# PCB_WOOD-WORKSHOP-REV1.net
KiCad netlist of a schematic drawn in Altium Designer
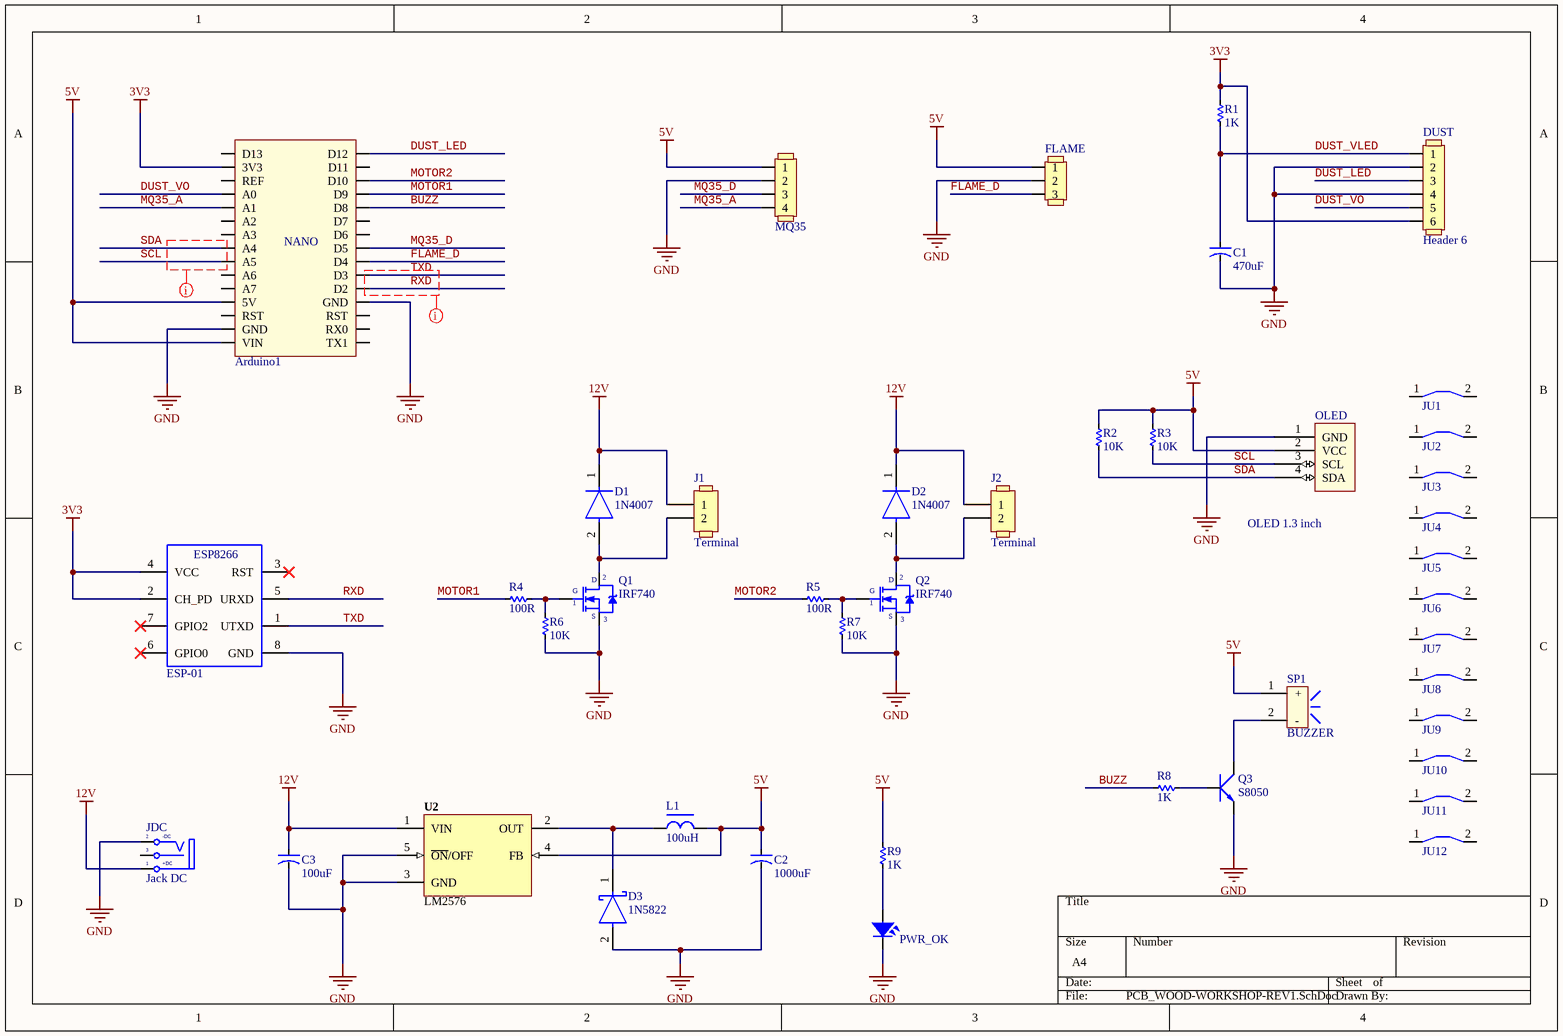
[diagram p0: PCB_WOOD-WORKSHOP-REV1.SchDoc]

(export (version "E")
  (design (tool "Eeschema 10.0.6"))
  (components
    (comp (ref "Arduino1")
      (value "Arduino Nano")
      (footprint "Arduino Nano")
      (description "Arduino NANO")
      (libsource (lib "LIBRARY_MuaLinhKien") (part "Arduino Nano"))
    )
    (comp (ref "C1")
      (value "470uF")
      (footprint "CA-ALU-6.3")
      (description "Capacitor (Semiconductor SIM Model)")
      (fields (field (name "PUBLISHER") "Altium Limited"))
      (libsource (lib "LIBRARY_MuaLinhKien") (part "CN-ALU-DIP"))
    )
    (comp (ref "C2")
      (value "1000uF")
      (footprint "CA-ALU-16")
      (description "Capacitor (Semiconductor SIM Model)")
      (fields (field (name "PUBLISHER") "Altium Limited"))
      (libsource (lib "LIBRARY_MuaLinhKien") (part "CN-ALU-DIP"))
    )
    (comp (ref "C3")
      (value "100uF")
      (footprint "CA-ALU-16")
      (description "Capacitor (Semiconductor SIM Model)")
      (fields (field (name "PUBLISHER") "Altium Limited"))
      (libsource (lib "LIBRARY_MuaLinhKien") (part "CN-ALU-DIP"))
    )
    (comp (ref "D1")
      (value "1N4007")
      (footprint "FP-1N4007-MFG")
      (description "Rectifier diode 1000 V 1 A DO-41, ,")
      (fields
        (field (name "MANUFACTURER") "Diotec")
        (field (name "OCTOPART") "https://octopart.com/1n4007-diotec-4040411")
      )
      (libsource (lib "Altium Content Vault") (part "d7152d700b627762746794eb795d46e"))
    )
    (comp (ref "D2")
      (value "1N4007")
      (footprint "FP-1N4007-MFG")
      (description "Rectifier diode 1000 V 1 A DO-41, ,")
      (fields
        (field (name "MANUFACTURER") "Diotec")
        (field (name "OCTOPART") "https://octopart.com/1n4007-diotec-4040411")
      )
      (libsource (lib "Altium Content Vault") (part "d7152d700b627762746794eb795d46e"))
    )
    (comp (ref "D3")
      (value "1N5822")
      (footprint "FP-DO-201AD-MFG")
      (description "DIODE SCHOTTKY 40V 3A DO201AD")
      (fields
        (field (name "OCTOPART") "https://octopart.com/1n5822-stmicroelectronics-323225")
        (field (name "MANUFACTURER") "STMicroelectronics")
      )
      (libsource (lib "Altium Content Vault") (part "1d6ec82d83fb6aee721767c19dac4b9"))
    )
    (comp (ref "DUST") (value "Header 6") (footprint "HEADER x6") (libsource (lib "Duc") (part "Header 6")))
    (comp (ref "FLAME") (value "Header 3") (footprint "HEADER x3") (libsource (lib "Duc") (part "Header 3")))
    (comp (ref "J1")
      (value "Terminal")
      (footprint "Terminal x2 5mm")
      (description "Terminal x2")
      (libsource (lib "Duc") (part "Terminal x2"))
    )
    (comp (ref "J2")
      (value "Terminal")
      (footprint "Terminal x2 5mm")
      (description "Terminal x2")
      (libsource (lib "Duc") (part "Terminal x2"))
    )
    (comp (ref "JDC")
      (value "Jack DC")
      (footprint "DC0")
      (description "Jac DC input")
      (libsource (lib "LIBRARY_MuaLinhKien") (part "DCIN"))
    )
    (comp (ref "JU1")
      (value "JUMPER 5MM")
      (footprint "JUMPER 10MM")
      (libsource (lib "tunaSchlib") (part "JUMPER 5MM"))
    )
    (comp (ref "JU2")
      (value "JUMPER 5MM")
      (footprint "JUMPER 10MM")
      (libsource (lib "tunaSchlib") (part "JUMPER 5MM"))
    )
    (comp (ref "JU3")
      (value "JUMPER 5MM")
      (footprint "JUMPER 10MM")
      (libsource (lib "tunaSchlib") (part "JUMPER 5MM"))
    )
    (comp (ref "JU4")
      (value "JUMPER 5MM")
      (footprint "JUMPER 5MM")
      (libsource (lib "tunaSchlib") (part "JUMPER 5MM"))
    )
    (comp (ref "JU5")
      (value "JUMPER 5MM")
      (footprint "JUMPER 5MM")
      (libsource (lib "tunaSchlib") (part "JUMPER 5MM"))
    )
    (comp (ref "JU6")
      (value "JUMPER 5MM")
      (footprint "JUMPER 15MM")
      (libsource (lib "tunaSchlib") (part "JUMPER 5MM"))
    )
    (comp (ref "JU7")
      (value "JUMPER 5MM")
      (footprint "JUMPER 15MM")
      (libsource (lib "tunaSchlib") (part "JUMPER 5MM"))
    )
    (comp (ref "JU8")
      (value "JUMPER 5MM")
      (footprint "JUMPER 10MM")
      (libsource (lib "tunaSchlib") (part "JUMPER 5MM"))
    )
    (comp (ref "JU9")
      (value "JUMPER 5MM")
      (footprint "JUMPER 5MM")
      (libsource (lib "tunaSchlib") (part "JUMPER 5MM"))
    )
    (comp (ref "JU10")
      (value "JUMPER 5MM")
      (footprint "JUMPER 15MM")
      (libsource (lib "tunaSchlib") (part "JUMPER 5MM"))
    )
    (comp (ref "JU11")
      (value "JUMPER 5MM")
      (footprint "JUMPER 10MM")
      (libsource (lib "tunaSchlib") (part "JUMPER 5MM"))
    )
    (comp (ref "JU12")
      (value "JUMPER 5MM")
      (footprint "JUMPER 15MM")
      (libsource (lib "tunaSchlib") (part "JUMPER 5MM"))
    )
    (comp (ref "L1")
      (value "100uH")
      (footprint "L-DIP-M-8")
      (description "Inductor")
      (libsource (lib "LIBRARY_MuaLinhKien") (part "L-DIP-1"))
    )
    (comp (ref "MQ35") (value "Header 4") (footprint "HEADER x4") (libsource (lib "Duc") (part "Header 4")))
    (comp (ref "OLED")
      (value "OLED 1.3 inch")
      (footprint "OLED 0.96 inch")
      (libsource (lib "tunaSchlib") (part "OLED 0.96 inch"))
    )
    (comp (ref "PWR_OK")
      (value "LED")
      (footprint "LED-5-RED")
      (description "LED Single colour Green and Red")
      (libsource (lib "LIBRARY_MuaLinhKien") (part "LED"))
    )
    (comp (ref "Q1")
      (value "IRF740")
      (footprint "TO220H1")
      (description "MOSFET N - CHANNEL 500V - 0.75 - 8A - TO-220")
      (libsource (lib "LIBRARY_MuaLinhKien") (part "IRF840"))
    )
    (comp (ref "Q2")
      (value "IRF740")
      (footprint "TO220H1")
      (description "MOSFET N - CHANNEL 500V - 0.75 - 8A - TO-220")
      (libsource (lib "LIBRARY_MuaLinhKien") (part "IRF840"))
    )
    (comp (ref "Q3")
      (value "S8050")
      (footprint "TO92-123")
      (description "NPN 600mW, ECB")
      (libsource (lib "LIBRARY_MuaLinhKien") (part "2SC1815"))
    )
    (comp (ref "R1")
      (value "1K")
      (footprint "RES-1/4W")
      (description "Res")
      (fields
        (field (name "MANUFACTURER") "Generic Components")
        (field (name "PUBLISHER") "Altium Hobart Technology Centre")
      )
      (libsource (lib "LIBRARY_MuaLinhKien") (part "Res"))
    )
    (comp (ref "R2")
      (value "10K")
      (footprint "RES-1/4W")
      (description "Res")
      (fields
        (field (name "MANUFACTURER") "Generic Components")
        (field (name "PUBLISHER") "Altium Hobart Technology Centre")
      )
      (libsource (lib "LIBRARY_MuaLinhKien") (part "Res"))
    )
    (comp (ref "R3")
      (value "10K")
      (footprint "RES-1/4W")
      (description "Res")
      (fields
        (field (name "MANUFACTURER") "Generic Components")
        (field (name "PUBLISHER") "Altium Hobart Technology Centre")
      )
      (libsource (lib "LIBRARY_MuaLinhKien") (part "Res"))
    )
    (comp (ref "R4")
      (value "100R")
      (footprint "RES-1/4W")
      (description "Res")
      (fields
        (field (name "MANUFACTURER") "Generic Components")
        (field (name "PUBLISHER") "Altium Hobart Technology Centre")
      )
      (libsource (lib "LIBRARY_MuaLinhKien") (part "Res"))
    )
    (comp (ref "R5")
      (value "100R")
      (footprint "RES-1/4W")
      (description "Res")
      (fields
        (field (name "MANUFACTURER") "Generic Components")
        (field (name "PUBLISHER") "Altium Hobart Technology Centre")
      )
      (libsource (lib "LIBRARY_MuaLinhKien") (part "Res"))
    )
    (comp (ref "R6")
      (value "10K")
      (footprint "RES-1/4W")
      (description "Res")
      (fields
        (field (name "MANUFACTURER") "Generic Components")
        (field (name "PUBLISHER") "Altium Hobart Technology Centre")
      )
      (libsource (lib "LIBRARY_MuaLinhKien") (part "Res"))
    )
    (comp (ref "R7")
      (value "10K")
      (footprint "RES-1/4W")
      (description "Res")
      (fields
        (field (name "MANUFACTURER") "Generic Components")
        (field (name "PUBLISHER") "Altium Hobart Technology Centre")
      )
      (libsource (lib "LIBRARY_MuaLinhKien") (part "Res"))
    )
    (comp (ref "R8")
      (value "1K")
      (footprint "RES-1/4W")
      (description "Res")
      (fields
        (field (name "MANUFACTURER") "Generic Components")
        (field (name "PUBLISHER") "Altium Hobart Technology Centre")
      )
      (libsource (lib "LIBRARY_MuaLinhKien") (part "Res"))
    )
    (comp (ref "R9")
      (value "1K")
      (footprint "RES-1/4W")
      (description "Res")
      (fields
        (field (name "MANUFACTURER") "Generic Components")
        (field (name "PUBLISHER") "Altium Hobart Technology Centre")
      )
      (libsource (lib "LIBRARY_MuaLinhKien") (part "Res"))
    )
    (comp (ref "SP1")
      (value "BUZZER")
      (footprint "Buzzer 5V 9x1.2mm")
      (description "Buzzer through hole (3V3/5V/12V)")
      (libsource (lib "Duc") (part "Speaker"))
    )
    (comp (ref "U1")
      (value "ESP-01")
      (footprint "ESP8266")
      (description "ESP-12 Wi-Fi Module")
      (libsource (lib "LIBRARY_MuaLinhKien") (part "ESP8266-01"))
    )
    (comp (ref "U2")
      (value "LM2576")
      (footprint "DIP5-T")
      (libsource (lib "LIBRARY_MuaLinhKien") (part "LM2576"))
    )
  )
  (nets
    (net (code "1") (name "/BUZZ") (class "Default")
      (node (ref "Arduino1") (pin "D8") (pinfunction "D8_D8") (pintype "passive"))
      (node (ref "R8") (pin "2") (pinfunction "2_2") (pintype "passive"))
    )
    (net (code "2") (name "/DUST_LED") (class "Default")
      (node (ref "Arduino1") (pin "D12") (pinfunction "D12_D12") (pintype "passive"))
      (node (ref "DUST") (pin "3") (pinfunction "3_3") (pintype "passive"))
    )
    (net (code "3") (name "/DUST_VLED") (class "Default")
      (node (ref "C1") (pin "1") (pinfunction "1_1") (pintype "passive"))
      (node (ref "DUST") (pin "1") (pinfunction "1_1") (pintype "passive"))
      (node (ref "R1") (pin "2") (pinfunction "2_2") (pintype "passive"))
    )
    (net (code "4") (name "/DUST_VO") (class "Default")
      (node (ref "Arduino1") (pin "A0") (pinfunction "A0_A0") (pintype "passive"))
      (node (ref "DUST") (pin "5") (pinfunction "5_5") (pintype "passive"))
    )
    (net (code "5") (name "/FLAME_D") (class "Default")
      (node (ref "Arduino1") (pin "D4") (pinfunction "D4_D4") (pintype "passive"))
      (node (ref "FLAME") (pin "3") (pinfunction "3_3") (pintype "passive"))
    )
    (net (code "6") (name "/MOTOR1") (class "Default")
      (node (ref "Arduino1") (pin "D9") (pinfunction "D9_D9") (pintype "passive"))
      (node (ref "R4") (pin "2") (pinfunction "2_2") (pintype "passive"))
    )
    (net (code "7") (name "/MOTOR2") (class "Default")
      (node (ref "Arduino1") (pin "D10") (pinfunction "D10_D10") (pintype "passive"))
      (node (ref "R5") (pin "2") (pinfunction "2_2") (pintype "passive"))
    )
    (net (code "8") (name "/MQ35_A") (class "Default")
      (node (ref "Arduino1") (pin "A1") (pinfunction "A1_A1") (pintype "passive"))
      (node (ref "MQ35") (pin "4") (pinfunction "4_4") (pintype "passive"))
    )
    (net (code "9") (name "/MQ35_D") (class "Default")
      (node (ref "Arduino1") (pin "D5") (pinfunction "D5_D5") (pintype "passive"))
      (node (ref "MQ35") (pin "3") (pinfunction "3_3") (pintype "passive"))
    )
    (net (code "10") (name "/RXD") (class "Default")
      (node (ref "Arduino1") (pin "D2") (pinfunction "D2_D2") (pintype "passive"))
      (node (ref "U1") (pin "5") (pinfunction "URXD_5") (pintype "passive"))
    )
    (net (code "11") (name "/SCL") (class "Default")
      (node (ref "Arduino1") (pin "A5") (pinfunction "A5_A5") (pintype "passive"))
      (node (ref "OLED") (pin "3") (pinfunction "SCL_3") (pintype "bidirectional"))
      (node (ref "R3") (pin "2") (pinfunction "2_2") (pintype "passive"))
    )
    (net (code "12") (name "/SDA") (class "Default")
      (node (ref "Arduino1") (pin "A4") (pinfunction "A4_A4") (pintype "passive"))
      (node (ref "OLED") (pin "4") (pinfunction "SDA_4") (pintype "bidirectional"))
      (node (ref "R2") (pin "2") (pinfunction "2_2") (pintype "passive"))
    )
    (net (code "13") (name "/TXD") (class "Default")
      (node (ref "Arduino1") (pin "D3") (pinfunction "D3_D3") (pintype "passive"))
      (node (ref "U1") (pin "1") (pinfunction "UTXD_1") (pintype "passive"))
    )
    (net (code "14") (name "3V3") (class "Default")
      (node (ref "Arduino1") (pin "3V3") (pinfunction "3V3_3V3") (pintype "passive"))
      (node (ref "DUST") (pin "6") (pinfunction "6_6") (pintype "passive"))
      (node (ref "R1") (pin "1") (pinfunction "1_1") (pintype "passive"))
      (node (ref "U1") (pin "2") (pinfunction "CH_PD_2") (pintype "passive"))
      (node (ref "U1") (pin "4") (pinfunction "VCC_4") (pintype "passive"))
    )
    (net (code "15") (name "5V") (class "Default")
      (node (ref "Arduino1") (pin "5V") (pinfunction "5V_5V") (pintype "passive"))
      (node (ref "Arduino1") (pin "VIN") (pinfunction "VIN_VIN") (pintype "passive"))
      (node (ref "C2") (pin "1") (pinfunction "1_1") (pintype "passive"))
      (node (ref "FLAME") (pin "1") (pinfunction "1_1") (pintype "passive"))
      (node (ref "L1") (pin "2") (pinfunction "2_2") (pintype "passive"))
      (node (ref "MQ35") (pin "1") (pinfunction "1_1") (pintype "passive"))
      (node (ref "OLED") (pin "2") (pinfunction "VCC_2") (pintype "power_in"))
      (node (ref "R2") (pin "1") (pinfunction "1_1") (pintype "passive"))
      (node (ref "R3") (pin "1") (pinfunction "1_1") (pintype "passive"))
      (node (ref "R9") (pin "1") (pinfunction "1_1") (pintype "passive"))
      (node (ref "SP1") (pin "1") (pinfunction "+_1") (pintype "passive"))
      (node (ref "U2") (pin "4") (pinfunction "FB_4") (pintype "input"))
    )
    (net (code "16") (name "12V") (class "Default")
      (node (ref "C3") (pin "1") (pinfunction "1_1") (pintype "passive"))
      (node (ref "D1") (pin "1") (pinfunction "C_1") (pintype "passive"))
      (node (ref "D2") (pin "1") (pinfunction "C_1") (pintype "passive"))
      (node (ref "J1") (pin "1") (pinfunction "1_1") (pintype "passive"))
      (node (ref "J2") (pin "1") (pinfunction "1_1") (pintype "passive"))
      (node (ref "JDC") (pin "1") (pinfunction "T_1") (pintype "passive"))
      (node (ref "U2") (pin "1") (pinfunction "VIN_1") (pintype "power_in"))
    )
    (net (code "17") (name "GND") (class "Default")
      (node (ref "Arduino1") (pin "GND") (pinfunction "GND_GND") (pintype "passive"))
      (node (ref "C1") (pin "2") (pinfunction "2_2") (pintype "passive"))
      (node (ref "C2") (pin "2") (pinfunction "2_2") (pintype "passive"))
      (node (ref "C3") (pin "2") (pinfunction "2_2") (pintype "passive"))
      (node (ref "D3") (pin "2") (pinfunction "A_2") (pintype "passive"))
      (node (ref "DUST") (pin "2") (pinfunction "2_2") (pintype "passive"))
      (node (ref "DUST") (pin "4") (pinfunction "4_4") (pintype "passive"))
      (node (ref "FLAME") (pin "2") (pinfunction "2_2") (pintype "passive"))
      (node (ref "JDC") (pin "2") (pinfunction "TN_2") (pintype "passive"))
      (node (ref "MQ35") (pin "2") (pinfunction "2_2") (pintype "passive"))
      (node (ref "OLED") (pin "1") (pinfunction "GND_1") (pintype "power_in"))
      (node (ref "PWR_OK") (pin "2") (pinfunction "2_2") (pintype "passive"))
      (node (ref "Q1") (pin "3") (pinfunction "S_3") (pintype "passive"))
      (node (ref "Q2") (pin "3") (pinfunction "S_3") (pintype "passive"))
      (node (ref "Q3") (pin "1") (pinfunction "E_1") (pintype "passive"))
      (node (ref "R6") (pin "2") (pinfunction "2_2") (pintype "passive"))
      (node (ref "R7") (pin "2") (pinfunction "2_2") (pintype "passive"))
      (node (ref "U1") (pin "8") (pinfunction "GND_8") (pintype "passive"))
      (node (ref "U2") (pin "3") (pinfunction "GND_3") (pintype "power_in"))
      (node (ref "U2") (pin "5") (pinfunction "~{ON}/OFF_5") (pintype "input"))
    )
    (net (code "18") (name "Net-(D1-A)") (class "Default")
      (node (ref "D1") (pin "2") (pinfunction "A_2") (pintype "passive"))
      (node (ref "J1") (pin "2") (pinfunction "2_2") (pintype "passive"))
      (node (ref "Q1") (pin "2") (pinfunction "D_2") (pintype "passive"))
    )
    (net (code "19") (name "Net-(D2-A)") (class "Default")
      (node (ref "D2") (pin "2") (pinfunction "A_2") (pintype "passive"))
      (node (ref "J2") (pin "2") (pinfunction "2_2") (pintype "passive"))
      (node (ref "Q2") (pin "2") (pinfunction "D_2") (pintype "passive"))
    )
    (net (code "20") (name "Net-(D3-C)") (class "Default")
      (node (ref "D3") (pin "1") (pinfunction "C_1") (pintype "passive"))
      (node (ref "L1") (pin "1") (pinfunction "1_1") (pintype "passive"))
      (node (ref "U2") (pin "2") (pinfunction "OUT_2") (pintype "power_in"))
    )
    (net (code "21") (name "Net-(PWR_OK-Pad1)") (class "Default")
      (node (ref "PWR_OK") (pin "1") (pinfunction "1_1") (pintype "passive"))
      (node (ref "R9") (pin "2") (pinfunction "2_2") (pintype "passive"))
    )
    (net (code "22") (name "Net-(Q1-G)") (class "Default")
      (node (ref "Q1") (pin "1") (pinfunction "G_1") (pintype "passive"))
      (node (ref "R4") (pin "1") (pinfunction "1_1") (pintype "passive"))
      (node (ref "R6") (pin "1") (pinfunction "1_1") (pintype "passive"))
    )
    (net (code "23") (name "Net-(Q2-G)") (class "Default")
      (node (ref "Q2") (pin "1") (pinfunction "G_1") (pintype "passive"))
      (node (ref "R5") (pin "1") (pinfunction "1_1") (pintype "passive"))
      (node (ref "R7") (pin "1") (pinfunction "1_1") (pintype "passive"))
    )
    (net (code "24") (name "Net-(Q3-B)") (class "Default")
      (node (ref "Q3") (pin "3") (pinfunction "B_3") (pintype "passive"))
      (node (ref "R8") (pin "1") (pinfunction "1_1") (pintype "passive"))
    )
    (net (code "25") (name "Net-(Q3-C)") (class "Default")
      (node (ref "Q3") (pin "2") (pinfunction "C_2") (pintype "passive"))
      (node (ref "SP1") (pin "2") (pinfunction "-_2") (pintype "passive"))
    )
    (net (code "26") (name "unconnected-(Arduino1-PadA2)") (class "Default")
      (node (ref "Arduino1") (pin "A2") (pinfunction "A2_A2") (pintype "passive"))
    )
    (net (code "27") (name "unconnected-(Arduino1-PadA3)") (class "Default")
      (node (ref "Arduino1") (pin "A3") (pinfunction "A3_A3") (pintype "passive"))
    )
    (net (code "28") (name "unconnected-(Arduino1-PadA6)") (class "Default")
      (node (ref "Arduino1") (pin "A6") (pinfunction "A6_A6") (pintype "passive"))
    )
    (net (code "29") (name "unconnected-(Arduino1-PadA7)") (class "Default")
      (node (ref "Arduino1") (pin "A7") (pinfunction "A7_A7") (pintype "passive"))
    )
    (net (code "30") (name "unconnected-(Arduino1-PadD6)") (class "Default")
      (node (ref "Arduino1") (pin "D6") (pinfunction "D6_D6") (pintype "passive"))
    )
    (net (code "31") (name "unconnected-(Arduino1-PadD7)") (class "Default")
      (node (ref "Arduino1") (pin "D7") (pinfunction "D7_D7") (pintype "passive"))
    )
    (net (code "32") (name "unconnected-(Arduino1-PadD11)") (class "Default")
      (node (ref "Arduino1") (pin "D11") (pinfunction "D11_D11") (pintype "passive"))
    )
    (net (code "33") (name "unconnected-(Arduino1-PadD13)") (class "Default")
      (node (ref "Arduino1") (pin "D13") (pinfunction "D13_D13") (pintype "passive"))
    )
    (net (code "34") (name "unconnected-(Arduino1-PadREF)") (class "Default")
      (node (ref "Arduino1") (pin "REF") (pinfunction "REF_REF") (pintype "passive"))
    )
    (net (code "35") (name "unconnected-(Arduino1-PadRST)") (class "Default")
      (node (ref "Arduino1") (pin "RST") (pinfunction "RST_RST") (pintype "passive"))
    )
    (net (code "36") (name "unconnected-(Arduino1-PadRST)_1") (class "Default")
      (node (ref "Arduino1") (pin "RST") (pinfunction "RST_RST") (pintype "passive"))
    )
    (net (code "37") (name "unconnected-(Arduino1-PadRX0)") (class "Default")
      (node (ref "Arduino1") (pin "RX0") (pinfunction "RX0_RX0") (pintype "passive"))
    )
    (net (code "38") (name "unconnected-(Arduino1-PadTX1)") (class "Default")
      (node (ref "Arduino1") (pin "TX1") (pinfunction "TX1_TX1") (pintype "passive"))
    )
    (net (code "39") (name "unconnected-(JDC-S-Pad3)") (class "Default")
      (node (ref "JDC") (pin "3") (pinfunction "S_3") (pintype "power_in"))
    )
    (net (code "40") (name "unconnected-(JU1-Pad1)") (class "Default")
      (node (ref "JU1") (pin "1") (pinfunction "1_1") (pintype "power_in"))
    )
    (net (code "41") (name "unconnected-(JU1-Pad2)") (class "Default")
      (node (ref "JU1") (pin "2") (pinfunction "2_2") (pintype "power_in"))
    )
    (net (code "42") (name "unconnected-(JU2-Pad1)") (class "Default")
      (node (ref "JU2") (pin "1") (pinfunction "1_1") (pintype "power_in"))
    )
    (net (code "43") (name "unconnected-(JU2-Pad2)") (class "Default")
      (node (ref "JU2") (pin "2") (pinfunction "2_2") (pintype "power_in"))
    )
    (net (code "44") (name "unconnected-(JU3-Pad1)") (class "Default")
      (node (ref "JU3") (pin "1") (pinfunction "1_1") (pintype "power_in"))
    )
    (net (code "45") (name "unconnected-(JU3-Pad2)") (class "Default")
      (node (ref "JU3") (pin "2") (pinfunction "2_2") (pintype "power_in"))
    )
    (net (code "46") (name "unconnected-(JU4-Pad1)") (class "Default")
      (node (ref "JU4") (pin "1") (pinfunction "1_1") (pintype "power_in"))
    )
    (net (code "47") (name "unconnected-(JU4-Pad2)") (class "Default")
      (node (ref "JU4") (pin "2") (pinfunction "2_2") (pintype "power_in"))
    )
    (net (code "48") (name "unconnected-(JU5-Pad1)") (class "Default")
      (node (ref "JU5") (pin "1") (pinfunction "1_1") (pintype "power_in"))
    )
    (net (code "49") (name "unconnected-(JU5-Pad2)") (class "Default")
      (node (ref "JU5") (pin "2") (pinfunction "2_2") (pintype "power_in"))
    )
    (net (code "50") (name "unconnected-(JU6-Pad1)") (class "Default")
      (node (ref "JU6") (pin "1") (pinfunction "1_1") (pintype "power_in"))
    )
    (net (code "51") (name "unconnected-(JU6-Pad2)") (class "Default")
      (node (ref "JU6") (pin "2") (pinfunction "2_2") (pintype "power_in"))
    )
    (net (code "52") (name "unconnected-(JU7-Pad1)") (class "Default")
      (node (ref "JU7") (pin "1") (pinfunction "1_1") (pintype "power_in"))
    )
    (net (code "53") (name "unconnected-(JU7-Pad2)") (class "Default")
      (node (ref "JU7") (pin "2") (pinfunction "2_2") (pintype "power_in"))
    )
    (net (code "54") (name "unconnected-(JU8-Pad1)") (class "Default")
      (node (ref "JU8") (pin "1") (pinfunction "1_1") (pintype "power_in"))
    )
    (net (code "55") (name "unconnected-(JU8-Pad2)") (class "Default")
      (node (ref "JU8") (pin "2") (pinfunction "2_2") (pintype "power_in"))
    )
    (net (code "56") (name "unconnected-(JU9-Pad1)") (class "Default")
      (node (ref "JU9") (pin "1") (pinfunction "1_1") (pintype "power_in"))
    )
    (net (code "57") (name "unconnected-(JU9-Pad2)") (class "Default")
      (node (ref "JU9") (pin "2") (pinfunction "2_2") (pintype "power_in"))
    )
    (net (code "58") (name "unconnected-(JU10-Pad1)") (class "Default")
      (node (ref "JU10") (pin "1") (pinfunction "1_1") (pintype "power_in"))
    )
    (net (code "59") (name "unconnected-(JU10-Pad2)") (class "Default")
      (node (ref "JU10") (pin "2") (pinfunction "2_2") (pintype "power_in"))
    )
    (net (code "60") (name "unconnected-(JU11-Pad1)") (class "Default")
      (node (ref "JU11") (pin "1") (pinfunction "1_1") (pintype "power_in"))
    )
    (net (code "61") (name "unconnected-(JU11-Pad2)") (class "Default")
      (node (ref "JU11") (pin "2") (pinfunction "2_2") (pintype "power_in"))
    )
    (net (code "62") (name "unconnected-(JU12-Pad1)") (class "Default")
      (node (ref "JU12") (pin "1") (pinfunction "1_1") (pintype "power_in"))
    )
    (net (code "63") (name "unconnected-(JU12-Pad2)") (class "Default")
      (node (ref "JU12") (pin "2") (pinfunction "2_2") (pintype "power_in"))
    )
    (net (code "64") (name "unconnected-(U1-GPIO0-Pad6)") (class "Default")
      (node (ref "U1") (pin "6") (pinfunction "GPIO0_6") (pintype "passive+no_connect"))
    )
    (net (code "65") (name "unconnected-(U1-GPIO2-Pad7)") (class "Default")
      (node (ref "U1") (pin "7") (pinfunction "GPIO2_7") (pintype "passive+no_connect"))
    )
    (net (code "66") (name "unconnected-(U1-RST-Pad3)") (class "Default")
      (node (ref "U1") (pin "3") (pinfunction "RST_3") (pintype "passive+no_connect"))
    )
  )
)
